# StepTruck_Esquematico.net
KiCad netlist of a schematic drawn in EAGLE
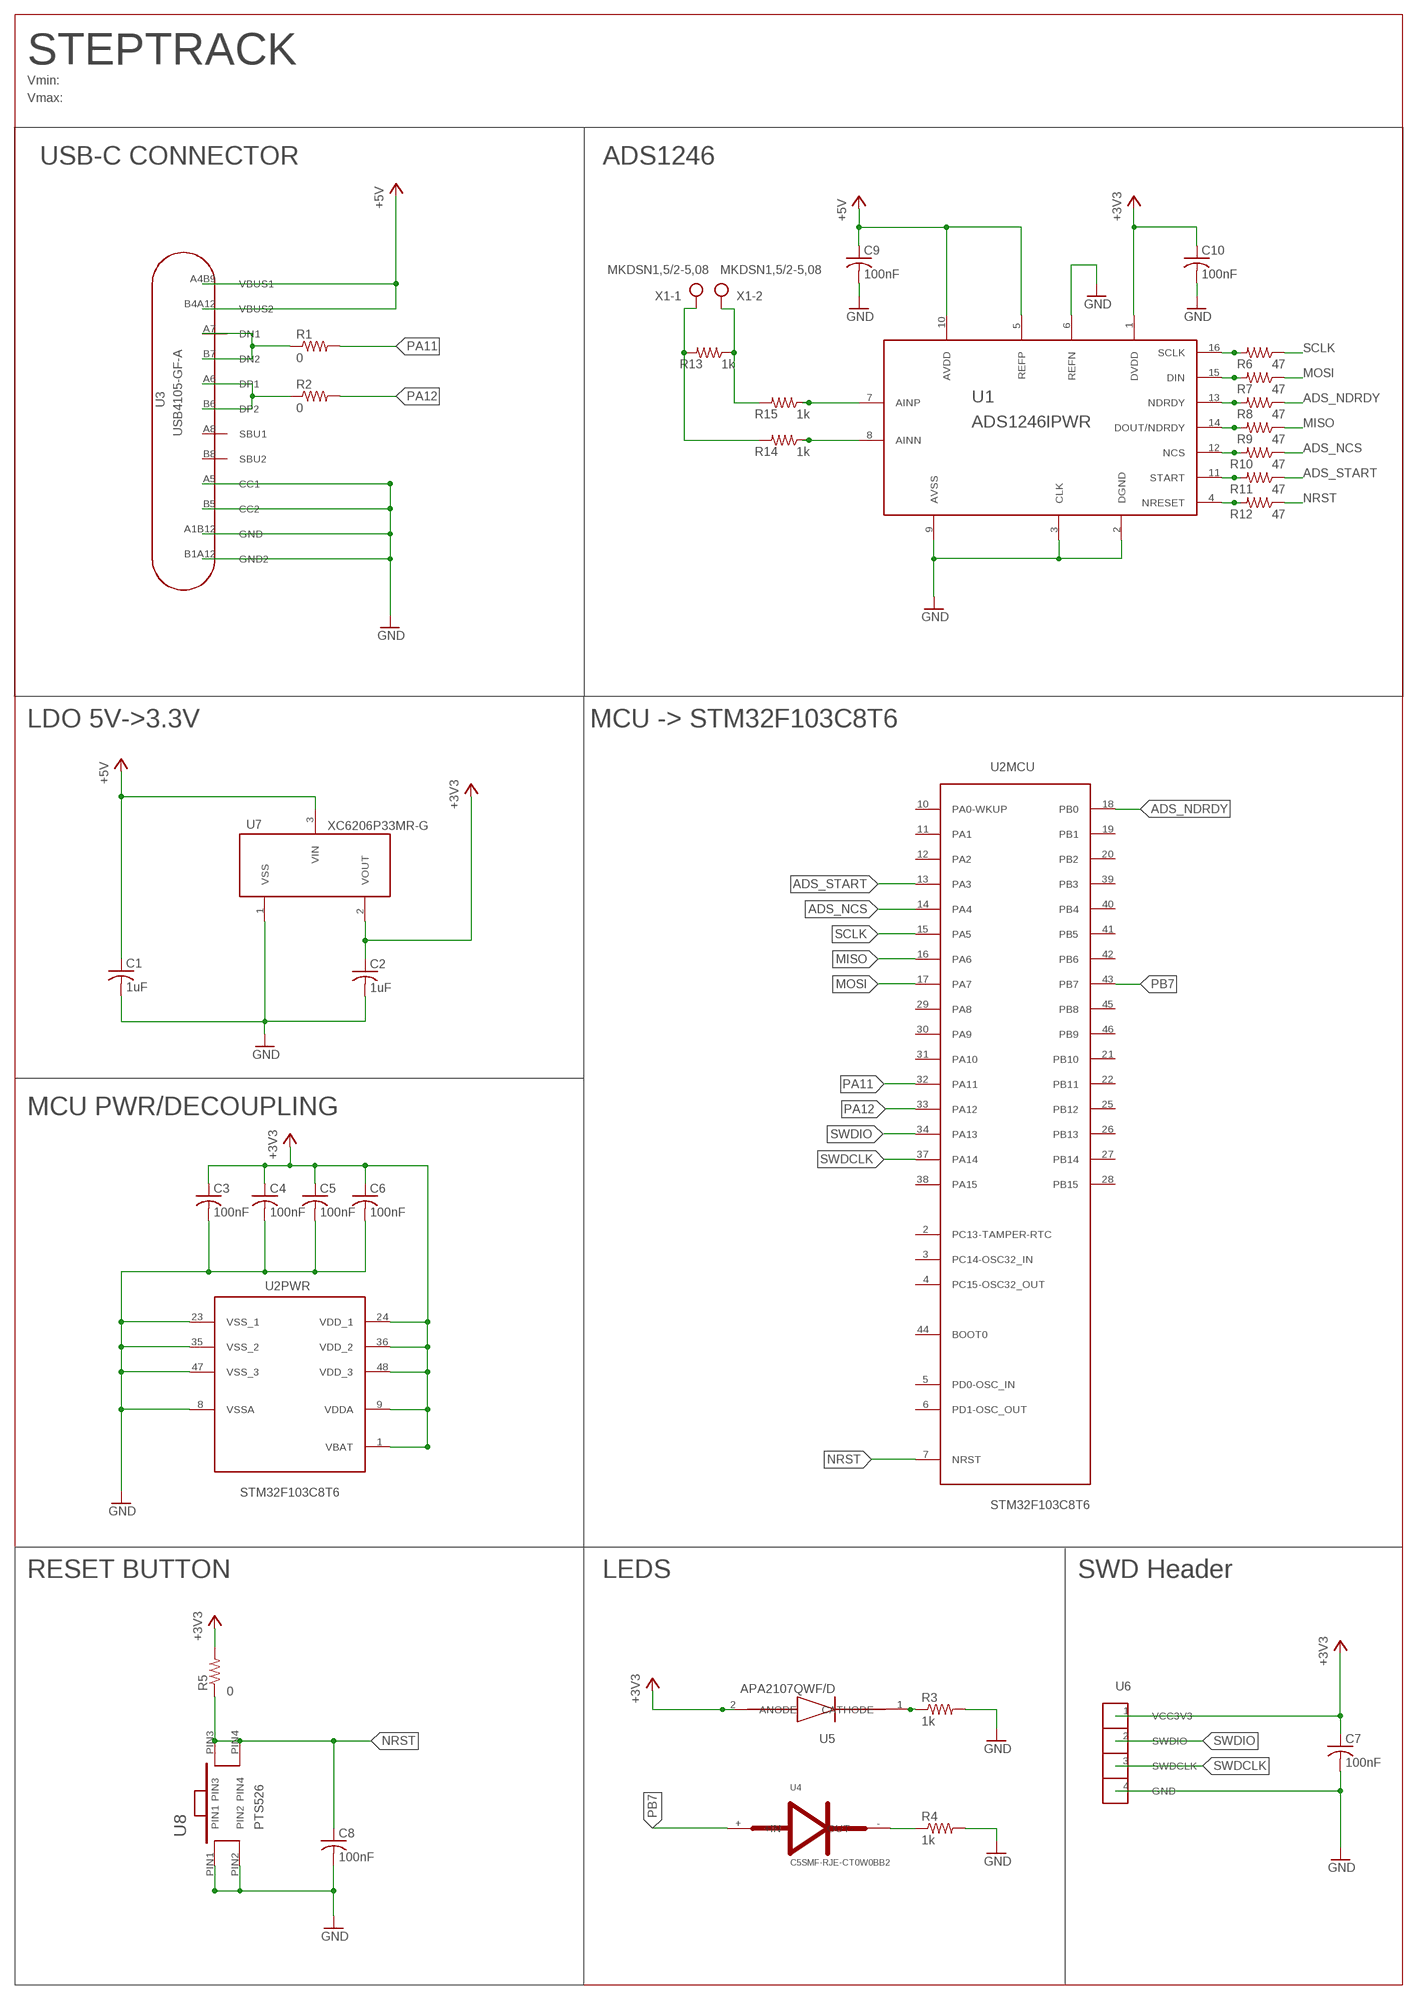
[diagram p0: schematic, sheet 1]

(export (version "E")
  (design (tool "Eeschema 10.0.6"))
  (components
    (comp (ref "C1")
      (value "1uF")
      (footprint "eagle-import:C0805K")
      (libsource (lib "eagle-import") (part "C-USC0805K"))
    )
    (comp (ref "C2")
      (value "1uF")
      (footprint "eagle-import:C0805K")
      (libsource (lib "eagle-import") (part "C-USC0805K"))
    )
    (comp (ref "C3")
      (value "100nF")
      (footprint "eagle-import:C0805K")
      (libsource (lib "eagle-import") (part "C-USC0805K"))
    )
    (comp (ref "C4")
      (value "100nF")
      (footprint "eagle-import:C0805K")
      (libsource (lib "eagle-import") (part "C-USC0805K"))
    )
    (comp (ref "C5")
      (value "100nF")
      (footprint "eagle-import:C0805K")
      (libsource (lib "eagle-import") (part "C-USC0805K"))
    )
    (comp (ref "C6")
      (value "100nF")
      (footprint "eagle-import:C0805K")
      (libsource (lib "eagle-import") (part "C-USC0805K"))
    )
    (comp (ref "C7")
      (value "100nF")
      (footprint "eagle-import:C0805K")
      (libsource (lib "eagle-import") (part "C-USC0805K"))
    )
    (comp (ref "C8")
      (value "100nF")
      (footprint "eagle-import:C0805K")
      (libsource (lib "eagle-import") (part "C-USC0805K"))
    )
    (comp (ref "C9")
      (value "100nF")
      (footprint "eagle-import:C0805K")
      (libsource (lib "eagle-import") (part "C-USC0805K"))
    )
    (comp (ref "C10")
      (value "100nF")
      (footprint "eagle-import:C0805K")
      (libsource (lib "eagle-import") (part "C-USC0805K"))
    )
    (comp (ref "R1")
      (value "0")
      (footprint "eagle-import:R0805")
      (libsource (lib "eagle-import") (part "R-US_R0805"))
    )
    (comp (ref "R2")
      (value "0")
      (footprint "eagle-import:R0805")
      (libsource (lib "eagle-import") (part "R-US_R0805"))
    )
    (comp (ref "R3")
      (value "1k")
      (footprint "eagle-import:R0805")
      (libsource (lib "eagle-import") (part "R-US_R0805"))
    )
    (comp (ref "R4")
      (value "1k")
      (footprint "eagle-import:R0805")
      (libsource (lib "eagle-import") (part "R-US_R0805"))
    )
    (comp (ref "R5")
      (value "0")
      (footprint "eagle-import:R0805")
      (libsource (lib "eagle-import") (part "R-US_R0805"))
    )
    (comp (ref "R6")
      (value "47")
      (footprint "eagle-import:R0805")
      (libsource (lib "eagle-import") (part "R-US_R0805"))
    )
    (comp (ref "R7")
      (value "47")
      (footprint "eagle-import:R0805")
      (libsource (lib "eagle-import") (part "R-US_R0805"))
    )
    (comp (ref "R8")
      (value "47")
      (footprint "eagle-import:R0805")
      (libsource (lib "eagle-import") (part "R-US_R0805"))
    )
    (comp (ref "R9")
      (value "47")
      (footprint "eagle-import:R0805")
      (libsource (lib "eagle-import") (part "R-US_R0805"))
    )
    (comp (ref "R10")
      (value "47")
      (footprint "eagle-import:R0805")
      (libsource (lib "eagle-import") (part "R-US_R0805"))
    )
    (comp (ref "R11")
      (value "47")
      (footprint "eagle-import:R0805")
      (libsource (lib "eagle-import") (part "R-US_R0805"))
    )
    (comp (ref "R12")
      (value "47")
      (footprint "eagle-import:R0805")
      (libsource (lib "eagle-import") (part "R-US_R0805"))
    )
    (comp (ref "R13")
      (value "1k")
      (footprint "eagle-import:R0805")
      (libsource (lib "eagle-import") (part "R-US_R0805"))
    )
    (comp (ref "R14")
      (value "1k")
      (footprint "eagle-import:R0805")
      (libsource (lib "eagle-import") (part "R-US_R0805"))
    )
    (comp (ref "R15")
      (value "1k")
      (footprint "eagle-import:R0805")
      (libsource (lib "eagle-import") (part "R-US_R0805"))
    )
    (comp (ref "U1")
      (value "ADS1246IPWR")
      (footprint "eagle-import:ADS1246IPWR")
      (libsource (lib "eagle-import") (part "ADS1246IPWR"))
    )
    (comp (ref "U2")
      (value "STM32F103C8T6")
      (footprint "eagle-import:48-LQFP")
      (libsource (lib "eagle-import") (part "STM32F103C8T6"))
    )
    (comp (ref "U3")
      (value "USB4105-GF-A")
      (footprint "eagle-import:USB4105-GF-A")
      (libsource (lib "eagle-import") (part "USB4105-GF-A"))
    )
    (comp (ref "U4")
      (value "C5SMF-RJE-CT0W0BB2")
      (footprint "eagle-import:C5SMF-RJE-CT0W0BB2")
      (libsource (lib "eagle-import") (part "C5SMF-RJE-CT0W0BB2"))
    )
    (comp (ref "U5")
      (value "APA2107QWF/D")
      (footprint "eagle-import:APA2107QWF_D")
      (libsource (lib "eagle-import") (part "APA2107QWF/D"))
    )
    (comp (ref "U6")
      (value "TS104TAA")
      (footprint "eagle-import:TS-104-T-AA")
      (libsource (lib "eagle-import") (part "TS104TAA"))
    )
    (comp (ref "U7")
      (value "XC6206P33MR-G")
      (footprint "eagle-import:SOT-23")
      (libsource (lib "eagle-import") (part "XC6206P33MR-G"))
    )
    (comp (ref "U8")
      (value "PTS526")
      (footprint "eagle-import:PTS526")
      (libsource (lib "eagle-import") (part "PTS526"))
    )
    (comp (ref "X1")
      (value "MKDSN1,5/2-5,08")
      (footprint "eagle-import:MKDSN1,5_2-5,08")
      (libsource (lib "eagle-import") (part "MKDSN1,5/2-5,08"))
    )
  )
  (nets
    (net (code "1") (name "+3V3") (class "Default")
      (node (ref "C10") (pin "1") (pinfunction "1_1") (pintype "passive"))
      (node (ref "C2") (pin "1") (pinfunction "1_1") (pintype "passive"))
      (node (ref "C3") (pin "1") (pinfunction "1_1") (pintype "passive"))
      (node (ref "C4") (pin "1") (pinfunction "1_1") (pintype "passive"))
      (node (ref "C5") (pin "1") (pinfunction "1_1") (pintype "passive"))
      (node (ref "C6") (pin "1") (pinfunction "1_1") (pintype "passive"))
      (node (ref "C7") (pin "1") (pinfunction "1_1") (pintype "passive"))
      (node (ref "R5") (pin "2") (pinfunction "2_2") (pintype "passive"))
      (node (ref "U1") (pin "1") (pinfunction "DVDD_1") (pintype "power_in"))
      (node (ref "U2") (pin "1") (pinfunction "VBAT_1") (pintype "power_in"))
      (node (ref "U2") (pin "24") (pinfunction "VDD_1_24") (pintype "power_in"))
      (node (ref "U2") (pin "36") (pinfunction "VDD_2_36") (pintype "power_in"))
      (node (ref "U2") (pin "48") (pinfunction "VDD_3_48") (pintype "power_in"))
      (node (ref "U2") (pin "9") (pinfunction "VDDA_9") (pintype "power_in"))
      (node (ref "U5") (pin "2") (pinfunction "ANODE_2") (pintype "bidirectional"))
      (node (ref "U6") (pin "1") (pinfunction "VCC3V3_1") (pintype "power_in"))
      (node (ref "U7") (pin "2") (pinfunction "VOUT_2") (pintype "power_in"))
    )
    (net (code "2") (name "+5V") (class "Default")
      (node (ref "C1") (pin "1") (pinfunction "1_1") (pintype "passive"))
      (node (ref "C9") (pin "1") (pinfunction "1_1") (pintype "passive"))
      (node (ref "U1") (pin "10") (pinfunction "AVDD_10") (pintype "power_in"))
      (node (ref "U1") (pin "5") (pinfunction "REFP_5") (pintype "input"))
      (node (ref "U3") (pin "A4B9") (pinfunction "VBUS1_A4B9") (pintype "power_in"))
      (node (ref "U3") (pin "B4A12") (pinfunction "VBUS2_B4A12") (pintype "power_in"))
      (node (ref "U7") (pin "3") (pinfunction "VIN_3") (pintype "power_in"))
    )
    (net (code "3") (name "ADS_NCS") (class "Default")
      (node (ref "R10") (pin "1") (pinfunction "1_1") (pintype "passive"))
      (node (ref "U2") (pin "14") (pinfunction "PA4_14") (pintype "bidirectional"))
    )
    (net (code "4") (name "ADS_NDRDY") (class "Default")
      (node (ref "R8") (pin "1") (pinfunction "1_1") (pintype "passive"))
      (node (ref "U2") (pin "18") (pinfunction "PB0_18") (pintype "bidirectional"))
    )
    (net (code "5") (name "ADS_START") (class "Default")
      (node (ref "R11") (pin "1") (pinfunction "1_1") (pintype "passive"))
      (node (ref "U2") (pin "13") (pinfunction "PA3_13") (pintype "bidirectional"))
    )
    (net (code "6") (name "GND") (class "Default")
      (node (ref "C1") (pin "2") (pinfunction "2_2") (pintype "passive"))
      (node (ref "C10") (pin "2") (pinfunction "2_2") (pintype "passive"))
      (node (ref "C2") (pin "2") (pinfunction "2_2") (pintype "passive"))
      (node (ref "C3") (pin "2") (pinfunction "2_2") (pintype "passive"))
      (node (ref "C4") (pin "2") (pinfunction "2_2") (pintype "passive"))
      (node (ref "C5") (pin "2") (pinfunction "2_2") (pintype "passive"))
      (node (ref "C6") (pin "2") (pinfunction "2_2") (pintype "passive"))
      (node (ref "C7") (pin "2") (pinfunction "2_2") (pintype "passive"))
      (node (ref "C8") (pin "2") (pinfunction "2_2") (pintype "passive"))
      (node (ref "C9") (pin "2") (pinfunction "2_2") (pintype "passive"))
      (node (ref "R3") (pin "2") (pinfunction "2_2") (pintype "passive"))
      (node (ref "R4") (pin "2") (pinfunction "2_2") (pintype "passive"))
      (node (ref "U1") (pin "2") (pinfunction "DGND_2") (pintype "bidirectional"))
      (node (ref "U1") (pin "3") (pinfunction "CLK_3") (pintype "input"))
      (node (ref "U1") (pin "6") (pinfunction "REFN_6") (pintype "input"))
      (node (ref "U1") (pin "9") (pinfunction "AVSS_9") (pintype "power_in"))
      (node (ref "U2") (pin "23") (pinfunction "VSS_1_23") (pintype "power_in"))
      (node (ref "U2") (pin "35") (pinfunction "VSS_2_35") (pintype "power_in"))
      (node (ref "U2") (pin "47") (pinfunction "VSS_3_47") (pintype "power_in"))
      (node (ref "U2") (pin "8") (pinfunction "VSSA_8") (pintype "power_in"))
      (node (ref "U3") (pin "A1B12") (pinfunction "GND_A1B12") (pintype "power_in"))
      (node (ref "U3") (pin "A5") (pinfunction "CC1_A5") (pintype "bidirectional"))
      (node (ref "U3") (pin "B1A12") (pinfunction "GND2_B1A12") (pintype "power_in"))
      (node (ref "U3") (pin "B5") (pinfunction "CC2_B5") (pintype "bidirectional"))
      (node (ref "U6") (pin "4") (pinfunction "GND_4") (pintype "power_in"))
      (node (ref "U7") (pin "1") (pinfunction "VSS_1") (pintype "power_in"))
      (node (ref "U8") (pin "PIN1") (pinfunction "PIN1_PIN1") (pintype "bidirectional"))
      (node (ref "U8") (pin "PIN2") (pinfunction "PIN2_PIN2") (pintype "bidirectional"))
    )
    (net (code "7") (name "MISO") (class "Default")
      (node (ref "R9") (pin "1") (pinfunction "1_1") (pintype "passive"))
      (node (ref "U2") (pin "16") (pinfunction "PA6_16") (pintype "bidirectional"))
    )
    (net (code "8") (name "MOSI") (class "Default")
      (node (ref "R7") (pin "1") (pinfunction "1_1") (pintype "passive"))
      (node (ref "U2") (pin "17") (pinfunction "PA7_17") (pintype "bidirectional"))
    )
    (net (code "9") (name "NRST") (class "Default")
      (node (ref "C8") (pin "1") (pinfunction "1_1") (pintype "passive"))
      (node (ref "R12") (pin "1") (pinfunction "1_1") (pintype "passive"))
      (node (ref "R5") (pin "1") (pinfunction "1_1") (pintype "passive"))
      (node (ref "U2") (pin "7") (pinfunction "NRST_7") (pintype "bidirectional"))
      (node (ref "U8") (pin "PIN3") (pinfunction "PIN3_PIN3") (pintype "bidirectional"))
      (node (ref "U8") (pin "PIN4") (pinfunction "PIN4_PIN4") (pintype "bidirectional"))
    )
    (net (code "10") (name "Net-(U1-AINN)") (class "Default")
      (node (ref "R14") (pin "1") (pinfunction "1_1") (pintype "passive"))
      (node (ref "U1") (pin "8") (pinfunction "AINN_8") (pintype "input"))
    )
    (net (code "11") (name "Net-(U1-AINP)") (class "Default")
      (node (ref "R15") (pin "1") (pinfunction "1_1") (pintype "passive"))
      (node (ref "U1") (pin "7") (pinfunction "AINP_7") (pintype "input"))
    )
    (net (code "12") (name "Net-(U1-DIN)") (class "Default")
      (node (ref "R7") (pin "2") (pinfunction "2_2") (pintype "passive"))
      (node (ref "U1") (pin "15") (pinfunction "DIN_15") (pintype "input"))
    )
    (net (code "13") (name "Net-(U1-DOUT{slash}NDRDY)") (class "Default")
      (node (ref "R9") (pin "2") (pinfunction "2_2") (pintype "passive"))
      (node (ref "U1") (pin "14") (pinfunction "DOUT/NDRDY_14") (pintype "output"))
    )
    (net (code "14") (name "Net-(U1-NCS)") (class "Default")
      (node (ref "R10") (pin "2") (pinfunction "2_2") (pintype "passive"))
      (node (ref "U1") (pin "12") (pinfunction "NCS_12") (pintype "input"))
    )
    (net (code "15") (name "Net-(U1-NDRDY)") (class "Default")
      (node (ref "R8") (pin "2") (pinfunction "2_2") (pintype "passive"))
      (node (ref "U1") (pin "13") (pinfunction "NDRDY_13") (pintype "output"))
    )
    (net (code "16") (name "Net-(U1-NRESET)") (class "Default")
      (node (ref "R12") (pin "2") (pinfunction "2_2") (pintype "passive"))
      (node (ref "U1") (pin "4") (pinfunction "NRESET_4") (pintype "input"))
    )
    (net (code "17") (name "Net-(U1-SCLK)") (class "Default")
      (node (ref "R6") (pin "2") (pinfunction "2_2") (pintype "passive"))
      (node (ref "U1") (pin "16") (pinfunction "SCLK_16") (pintype "input"))
    )
    (net (code "18") (name "Net-(U1-START)") (class "Default")
      (node (ref "R11") (pin "2") (pinfunction "2_2") (pintype "passive"))
      (node (ref "U1") (pin "11") (pinfunction "START_11") (pintype "input"))
    )
    (net (code "19") (name "Net-(U3-DN1)") (class "Default")
      (node (ref "R1") (pin "1") (pinfunction "1_1") (pintype "passive"))
      (node (ref "U3") (pin "A7") (pinfunction "DN1_A7") (pintype "bidirectional"))
      (node (ref "U3") (pin "B7") (pinfunction "DN2_B7") (pintype "bidirectional"))
    )
    (net (code "20") (name "Net-(U3-DP1)") (class "Default")
      (node (ref "R2") (pin "1") (pinfunction "1_1") (pintype "passive"))
      (node (ref "U3") (pin "A6") (pinfunction "DP1_A6") (pintype "bidirectional"))
      (node (ref "U3") (pin "B6") (pinfunction "DP2_B6") (pintype "bidirectional"))
    )
    (net (code "21") (name "Net-(U4-OUT-)") (class "Default")
      (node (ref "R4") (pin "1") (pinfunction "1_1") (pintype "passive"))
      (node (ref "U4") (pin "-") (pinfunction "OUT-_-") (pintype "passive"))
    )
    (net (code "22") (name "Net-(U5-CATHODE)") (class "Default")
      (node (ref "R3") (pin "1") (pinfunction "1_1") (pintype "passive"))
      (node (ref "U5") (pin "1") (pinfunction "CATHODE_1") (pintype "bidirectional"))
    )
    (net (code "23") (name "Net-(X1A-KL)") (class "Default")
      (node (ref "R13") (pin "2") (pinfunction "2_2") (pintype "passive"))
      (node (ref "R14") (pin "2") (pinfunction "2_2") (pintype "passive"))
      (node (ref "X1") (pin "1") (pinfunction "KL_1") (pintype "passive"))
    )
    (net (code "24") (name "Net-(X1B-KL)") (class "Default")
      (node (ref "R13") (pin "1") (pinfunction "1_1") (pintype "passive"))
      (node (ref "R15") (pin "2") (pinfunction "2_2") (pintype "passive"))
      (node (ref "X1") (pin "2") (pinfunction "KL_2") (pintype "passive"))
    )
    (net (code "25") (name "PA11") (class "Default")
      (node (ref "R1") (pin "2") (pinfunction "2_2") (pintype "passive"))
      (node (ref "U2") (pin "32") (pinfunction "PA11_32") (pintype "bidirectional"))
    )
    (net (code "26") (name "PA12") (class "Default")
      (node (ref "R2") (pin "2") (pinfunction "2_2") (pintype "passive"))
      (node (ref "U2") (pin "33") (pinfunction "PA12_33") (pintype "bidirectional"))
    )
    (net (code "27") (name "PB7") (class "Default")
      (node (ref "U2") (pin "43") (pinfunction "PB7_43") (pintype "bidirectional"))
      (node (ref "U4") (pin "+") (pinfunction "+IN_+") (pintype "passive"))
    )
    (net (code "28") (name "SCLK") (class "Default")
      (node (ref "R6") (pin "1") (pinfunction "1_1") (pintype "passive"))
      (node (ref "U2") (pin "15") (pinfunction "PA5_15") (pintype "bidirectional"))
    )
    (net (code "29") (name "SWDCLK") (class "Default")
      (node (ref "U2") (pin "37") (pinfunction "PA14_37") (pintype "bidirectional"))
      (node (ref "U6") (pin "3") (pinfunction "SWDCLK_3") (pintype "bidirectional"))
    )
    (net (code "30") (name "SWDIO") (class "Default")
      (node (ref "U2") (pin "34") (pinfunction "PA13_34") (pintype "bidirectional"))
      (node (ref "U6") (pin "2") (pinfunction "SWDIO_2") (pintype "bidirectional"))
    )
    (net (code "31") (name "unconnected-(U2A-BOOT0-Pad44)") (class "Default")
      (node (ref "U2") (pin "44") (pinfunction "BOOT0_44") (pintype "input"))
    )
    (net (code "32") (name "unconnected-(U2A-PA0-WKUP-Pad10)") (class "Default")
      (node (ref "U2") (pin "10") (pinfunction "PA0-WKUP_10") (pintype "bidirectional"))
    )
    (net (code "33") (name "unconnected-(U2A-PA1-Pad11)") (class "Default")
      (node (ref "U2") (pin "11") (pinfunction "PA1_11") (pintype "bidirectional"))
    )
    (net (code "34") (name "unconnected-(U2A-PA2-Pad12)") (class "Default")
      (node (ref "U2") (pin "12") (pinfunction "PA2_12") (pintype "bidirectional"))
    )
    (net (code "35") (name "unconnected-(U2A-PA8-Pad29)") (class "Default")
      (node (ref "U2") (pin "29") (pinfunction "PA8_29") (pintype "bidirectional"))
    )
    (net (code "36") (name "unconnected-(U2A-PA9-Pad30)") (class "Default")
      (node (ref "U2") (pin "30") (pinfunction "PA9_30") (pintype "bidirectional"))
    )
    (net (code "37") (name "unconnected-(U2A-PA10-Pad31)") (class "Default")
      (node (ref "U2") (pin "31") (pinfunction "PA10_31") (pintype "bidirectional"))
    )
    (net (code "38") (name "unconnected-(U2A-PA15-Pad38)") (class "Default")
      (node (ref "U2") (pin "38") (pinfunction "PA15_38") (pintype "bidirectional"))
    )
    (net (code "39") (name "unconnected-(U2A-PB1-Pad19)") (class "Default")
      (node (ref "U2") (pin "19") (pinfunction "PB1_19") (pintype "bidirectional"))
    )
    (net (code "40") (name "unconnected-(U2A-PB2-Pad20)") (class "Default")
      (node (ref "U2") (pin "20") (pinfunction "PB2_20") (pintype "bidirectional"))
    )
    (net (code "41") (name "unconnected-(U2A-PB3-Pad39)") (class "Default")
      (node (ref "U2") (pin "39") (pinfunction "PB3_39") (pintype "bidirectional"))
    )
    (net (code "42") (name "unconnected-(U2A-PB4-Pad40)") (class "Default")
      (node (ref "U2") (pin "40") (pinfunction "PB4_40") (pintype "bidirectional"))
    )
    (net (code "43") (name "unconnected-(U2A-PB5-Pad41)") (class "Default")
      (node (ref "U2") (pin "41") (pinfunction "PB5_41") (pintype "bidirectional"))
    )
    (net (code "44") (name "unconnected-(U2A-PB6-Pad42)") (class "Default")
      (node (ref "U2") (pin "42") (pinfunction "PB6_42") (pintype "bidirectional"))
    )
    (net (code "45") (name "unconnected-(U2A-PB8-Pad45)") (class "Default")
      (node (ref "U2") (pin "45") (pinfunction "PB8_45") (pintype "bidirectional"))
    )
    (net (code "46") (name "unconnected-(U2A-PB9-Pad46)") (class "Default")
      (node (ref "U2") (pin "46") (pinfunction "PB9_46") (pintype "bidirectional"))
    )
    (net (code "47") (name "unconnected-(U2A-PB10-Pad21)") (class "Default")
      (node (ref "U2") (pin "21") (pinfunction "PB10_21") (pintype "bidirectional"))
    )
    (net (code "48") (name "unconnected-(U2A-PB11-Pad22)") (class "Default")
      (node (ref "U2") (pin "22") (pinfunction "PB11_22") (pintype "bidirectional"))
    )
    (net (code "49") (name "unconnected-(U2A-PB12-Pad25)") (class "Default")
      (node (ref "U2") (pin "25") (pinfunction "PB12_25") (pintype "bidirectional"))
    )
    (net (code "50") (name "unconnected-(U2A-PB13-Pad26)") (class "Default")
      (node (ref "U2") (pin "26") (pinfunction "PB13_26") (pintype "bidirectional"))
    )
    (net (code "51") (name "unconnected-(U2A-PB14-Pad27)") (class "Default")
      (node (ref "U2") (pin "27") (pinfunction "PB14_27") (pintype "bidirectional"))
    )
    (net (code "52") (name "unconnected-(U2A-PB15-Pad28)") (class "Default")
      (node (ref "U2") (pin "28") (pinfunction "PB15_28") (pintype "bidirectional"))
    )
    (net (code "53") (name "unconnected-(U2A-PC13-TAMPER-RTC-Pad2)") (class "Default")
      (node (ref "U2") (pin "2") (pinfunction "PC13-TAMPER-RTC_2") (pintype "bidirectional"))
    )
    (net (code "54") (name "unconnected-(U2A-PC14-OSC32_IN-Pad3)") (class "Default")
      (node (ref "U2") (pin "3") (pinfunction "PC14-OSC32_IN_3") (pintype "bidirectional"))
    )
    (net (code "55") (name "unconnected-(U2A-PC15-OSC32_OUT-Pad4)") (class "Default")
      (node (ref "U2") (pin "4") (pinfunction "PC15-OSC32_OUT_4") (pintype "bidirectional"))
    )
    (net (code "56") (name "unconnected-(U2A-PD0-OSC_IN-Pad5)") (class "Default")
      (node (ref "U2") (pin "5") (pinfunction "PD0-OSC_IN_5") (pintype "input"))
    )
    (net (code "57") (name "unconnected-(U2A-PD1-OSC_OUT-Pad6)") (class "Default")
      (node (ref "U2") (pin "6") (pinfunction "PD1-OSC_OUT_6") (pintype "output"))
    )
    (net (code "58") (name "unconnected-(U3-SBU1-PadA8)") (class "Default")
      (node (ref "U3") (pin "A8") (pinfunction "SBU1_A8") (pintype "no_connect"))
    )
    (net (code "59") (name "unconnected-(U3-SBU2-PadB8)") (class "Default")
      (node (ref "U3") (pin "B8") (pinfunction "SBU2_B8") (pintype "no_connect"))
    )
  )
)
